# Microcontroller.net
KiCad netlist of a schematic drawn in Altium Designer
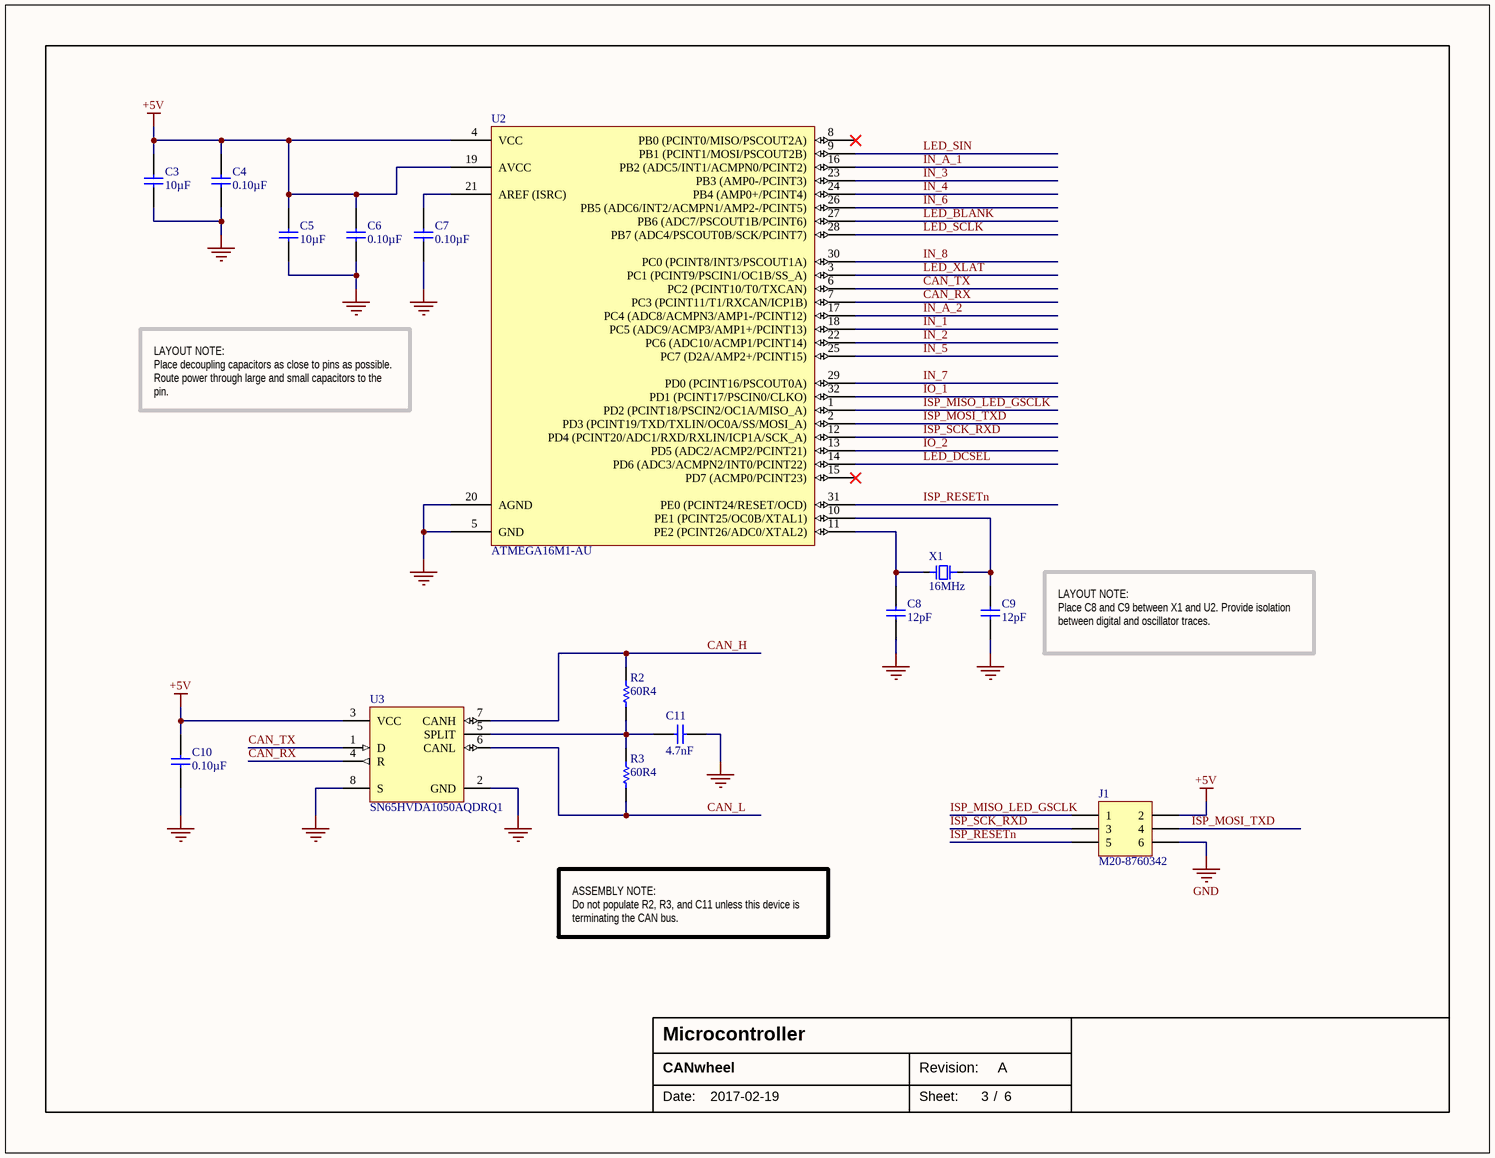
[diagram p0: Microcontroller.SchDoc]

(export (version "E")
  (design (tool "Eeschema 10.0.6"))
  (components
    (comp (ref "C3")
      (value "10µF")
      (footprint "CAP-0805-M")
      (fields
        (field (name "PART NUMBER") "CC0805KKX7R5BB106")
        (field (name "TOLERANCE") "±10%")
        (field (name "VOLTAGE") "6.3V")
      )
      (libsource (lib "Capacitors") (part "Capacitor"))
    )
    (comp (ref "C4")
      (value "0.10µF")
      (footprint "CAP-0402-M")
      (fields
        (field (name "PART NUMBER") "CC0402KRX7R5BB104")
        (field (name "TOLERANCE") "±10%")
        (field (name "VOLTAGE") "6.3V")
      )
      (libsource (lib "Capacitors") (part "Capacitor"))
    )
    (comp (ref "C5")
      (value "10µF")
      (footprint "CAP-0805-M")
      (fields
        (field (name "PART NUMBER") "CC0805KKX7R5BB106")
        (field (name "TOLERANCE") "±10%")
        (field (name "VOLTAGE") "6.3V")
      )
      (libsource (lib "Capacitors") (part "Capacitor"))
    )
    (comp (ref "C6")
      (value "0.10µF")
      (footprint "CAP-0402-M")
      (fields
        (field (name "PART NUMBER") "CC0402KRX7R5BB104")
        (field (name "TOLERANCE") "±10%")
        (field (name "VOLTAGE") "6.3V")
      )
      (libsource (lib "Capacitors") (part "Capacitor"))
    )
    (comp (ref "C7")
      (value "0.10µF")
      (footprint "CAP-0402-M")
      (fields
        (field (name "PART NUMBER") "CC0402KRX7R5BB104")
        (field (name "TOLERANCE") "±10%")
        (field (name "VOLTAGE") "6.3V")
      )
      (libsource (lib "Capacitors") (part "Capacitor"))
    )
    (comp (ref "C8")
      (value "12pF")
      (footprint "CAP-0402-M")
      (fields
        (field (name "PART NUMBER") "CC0402JRNPO9BN120")
        (field (name "TOLERANCE") "±5%")
        (field (name "VOLTAGE") "50V")
      )
      (libsource (lib "Capacitors") (part "Capacitor"))
    )
    (comp (ref "C9")
      (value "12pF")
      (footprint "CAP-0402-M")
      (fields
        (field (name "PART NUMBER") "CC0402JRNPO9BN120")
        (field (name "TOLERANCE") "±5%")
        (field (name "VOLTAGE") "50V")
      )
      (libsource (lib "Capacitors") (part "Capacitor"))
    )
    (comp (ref "C10")
      (value "0.10µF")
      (footprint "CAP-0402-M")
      (fields
        (field (name "PART NUMBER") "CC0402KRX7R5BB104")
        (field (name "TOLERANCE") "±10%")
        (field (name "VOLTAGE") "6.3V")
      )
      (libsource (lib "Capacitors") (part "Capacitor"))
    )
    (comp (ref "C11")
      (value "4.7nF")
      (footprint "CAP-0402-M")
      (fields
        (field (name "PART NUMBER") "CC0402KRX7R7BB472")
        (field (name "TOLERANCE") "±10%")
        (field (name "VOLTAGE") "16V")
      )
      (libsource (lib "Capacitors") (part "Capacitor"))
    )
    (comp (ref "J1")
      (value "M20-8760342")
      (footprint "M20-8760342")
      (libsource (lib "Connectors") (part "M20-8760342"))
    )
    (comp (ref "R2")
      (value "60R4")
      (footprint "RES-0805-M")
      (fields
        (field (name "PART NUMBER") "RC0805FR-0760R4L")
        (field (name "TOLERANCE") "1%")
        (field (name "POWER") "1/8 W")
      )
      (libsource (lib "Resistors") (part "Resistor"))
    )
    (comp (ref "R3")
      (value "60R4")
      (footprint "RES-0805-M")
      (fields
        (field (name "PART NUMBER") "RC0805FR-0760R4L")
        (field (name "TOLERANCE") "1%")
        (field (name "POWER") "1/8 W")
      )
      (libsource (lib "Resistors") (part "Resistor"))
    )
    (comp (ref "U2")
      (value "ATMEGA16M1-AU")
      (footprint "TQFP80P900X900X120-32N")
      (description "ATmega16M1 32-QFP 7x7 mm")
      (libsource (lib "CANwheel") (part "ATMEGA16M1-AU"))
    )
    (comp (ref "U3")
      (value "SN65HVDA1050AQDRQ1")
      (footprint "SOIC127P600X175-8M")
      (description "CAN transceiver")
      (libsource (lib "CANwheel") (part "SN65HVDA1050AQDRQ1"))
    )
    (comp (ref "X1")
      (value "16MHz")
      (footprint "SON127P500X135-2N")
      (description "SMD Crystal Oscillator 12 pF")
      (fields (field (name "Comment") "7A-16.000MAAE-T"))
      (libsource (lib "CANio") (part "7A-16.000MAAE-T"))
    )
  )
  (nets
    (net (code "1") (name "+5V") (class "Default")
      (node (ref "C10") (pin "1") (pinfunction "1_1") (pintype "passive"))
      (node (ref "C3") (pin "1") (pinfunction "1_1") (pintype "passive"))
      (node (ref "C4") (pin "1") (pinfunction "1_1") (pintype "passive"))
      (node (ref "C5") (pin "1") (pinfunction "1_1") (pintype "passive"))
      (node (ref "C6") (pin "1") (pinfunction "1_1") (pintype "passive"))
      (node (ref "J1") (pin "2") (pinfunction "2_2") (pintype "passive"))
      (node (ref "U2") (pin "19") (pinfunction "AVCC_19") (pintype "power_in"))
      (node (ref "U2") (pin "4") (pinfunction "VCC_4") (pintype "power_in"))
      (node (ref "U3") (pin "3") (pinfunction "VCC_3") (pintype "power_in"))
    )
    (net (code "2") (name "/CAN_H") (class "Default")
      (node (ref "R2") (pin "1") (pinfunction "1_1") (pintype "passive"))
      (node (ref "U3") (pin "7") (pinfunction "CANH_7") (pintype "bidirectional"))
    )
    (net (code "3") (name "/CAN_L") (class "Default")
      (node (ref "R3") (pin "1") (pinfunction "1_1") (pintype "passive"))
      (node (ref "U3") (pin "6") (pinfunction "CANL_6") (pintype "bidirectional"))
    )
    (net (code "4") (name "/CAN_RX") (class "Default")
      (node (ref "U2") (pin "7") (pinfunction "PC3_(PCINT11/T1/RXCAN/ICP1B)_7") (pintype "bidirectional"))
      (node (ref "U3") (pin "4") (pinfunction "R_4") (pintype "output"))
    )
    (net (code "5") (name "/CAN_TX") (class "Default")
      (node (ref "U2") (pin "6") (pinfunction "PC2_(PCINT10/T0/TXCAN)_6") (pintype "bidirectional"))
      (node (ref "U3") (pin "1") (pinfunction "D_1") (pintype "input"))
    )
    (net (code "6") (name "/IN_1") (class "Default")
      (node (ref "U2") (pin "18") (pinfunction "PC5_(ADC9/ACMP3/AMP1+/PCINT13)_18") (pintype "bidirectional"))
    )
    (net (code "7") (name "/IN_2") (class "Default")
      (node (ref "U2") (pin "22") (pinfunction "PC6_(ADC10/ACMP1/PCINT14)_22") (pintype "bidirectional"))
    )
    (net (code "8") (name "/IN_3") (class "Default")
      (node (ref "U2") (pin "23") (pinfunction "PB3_(AMP0-/PCINT3)_23") (pintype "bidirectional"))
    )
    (net (code "9") (name "/IN_4") (class "Default")
      (node (ref "U2") (pin "24") (pinfunction "PB4_(AMP0+/PCINT4)_24") (pintype "bidirectional"))
    )
    (net (code "10") (name "/IN_5") (class "Default")
      (node (ref "U2") (pin "25") (pinfunction "PC7_(D2A/AMP2+/PCINT15)_25") (pintype "bidirectional"))
    )
    (net (code "11") (name "/IN_6") (class "Default")
      (node (ref "U2") (pin "26") (pinfunction "PB5_(ADC6/INT2/ACMPN1/AMP2-/PCINT5)_26") (pintype "bidirectional"))
    )
    (net (code "12") (name "/IN_7") (class "Default")
      (node (ref "U2") (pin "29") (pinfunction "PD0_(PCINT16/PSCOUT0A)_29") (pintype "bidirectional"))
    )
    (net (code "13") (name "/IN_8") (class "Default")
      (node (ref "U2") (pin "30") (pinfunction "PC0_(PCINT8/INT3/PSCOUT1A)_30") (pintype "bidirectional"))
    )
    (net (code "14") (name "/IN_A_1") (class "Default")
      (node (ref "U2") (pin "16") (pinfunction "PB2_(ADC5/INT1/ACMPN0/PCINT2)_16") (pintype "bidirectional"))
    )
    (net (code "15") (name "/IN_A_2") (class "Default")
      (node (ref "U2") (pin "17") (pinfunction "PC4_(ADC8/ACMPN3/AMP1-/PCINT12)_17") (pintype "bidirectional"))
    )
    (net (code "16") (name "/IO_1") (class "Default")
      (node (ref "U2") (pin "32") (pinfunction "PD1_(PCINT17/PSCIN0/CLKO)_32") (pintype "bidirectional"))
    )
    (net (code "17") (name "/IO_2") (class "Default")
      (node (ref "U2") (pin "13") (pinfunction "PD5_(ADC2/ACMP2/PCINT21)_13") (pintype "bidirectional"))
    )
    (net (code "18") (name "/ISP_MISO_LED_GSCLK") (class "Default")
      (node (ref "J1") (pin "1") (pinfunction "1_1") (pintype "passive"))
      (node (ref "U2") (pin "1") (pinfunction "PD2_(PCINT18/PSCIN2/OC1A/MISO_A)_1") (pintype "bidirectional"))
    )
    (net (code "19") (name "/ISP_MOSI_TXD") (class "Default")
      (node (ref "J1") (pin "4") (pinfunction "4_4") (pintype "passive"))
      (node (ref "U2") (pin "2") (pinfunction "PD3_(PCINT19/TXD/TXLIN/OC0A/SS/MOSI_A)_2") (pintype "bidirectional"))
    )
    (net (code "20") (name "/ISP_RESETn") (class "Default")
      (node (ref "J1") (pin "5") (pinfunction "5_5") (pintype "passive"))
      (node (ref "U2") (pin "31") (pinfunction "PE0_(PCINT24/RESET/OCD)_31") (pintype "bidirectional"))
    )
    (net (code "21") (name "/ISP_SCK_RXD") (class "Default")
      (node (ref "J1") (pin "3") (pinfunction "3_3") (pintype "passive"))
      (node (ref "U2") (pin "12") (pinfunction "PD4_(PCINT20/ADC1/RXD/RXLIN/ICP1A/SCK_A)_12") (pintype "bidirectional"))
    )
    (net (code "22") (name "/LED_BLANK") (class "Default")
      (node (ref "U2") (pin "27") (pinfunction "PB6_(ADC7/PSCOUT1B/PCINT6)_27") (pintype "bidirectional"))
    )
    (net (code "23") (name "/LED_DCSEL") (class "Default")
      (node (ref "U2") (pin "14") (pinfunction "PD6_(ADC3/ACMPN2/INT0/PCINT22)_14") (pintype "bidirectional"))
    )
    (net (code "24") (name "/LED_SCLK") (class "Default")
      (node (ref "U2") (pin "28") (pinfunction "PB7_(ADC4/PSCOUT0B/SCK/PCINT7)_28") (pintype "bidirectional"))
    )
    (net (code "25") (name "/LED_SIN") (class "Default")
      (node (ref "U2") (pin "9") (pinfunction "PB1_(PCINT1/MOSI/PSCOUT2B)_9") (pintype "bidirectional"))
    )
    (net (code "26") (name "/LED_XLAT") (class "Default")
      (node (ref "U2") (pin "3") (pinfunction "PC1_(PCINT9/PSCIN1/OC1B/SS_A)_3") (pintype "bidirectional"))
    )
    (net (code "27") (name "GND") (class "Default")
      (node (ref "C10") (pin "2") (pinfunction "2_2") (pintype "passive"))
      (node (ref "C11") (pin "1") (pinfunction "1_1") (pintype "passive"))
      (node (ref "C3") (pin "2") (pinfunction "2_2") (pintype "passive"))
      (node (ref "C4") (pin "2") (pinfunction "2_2") (pintype "passive"))
      (node (ref "C5") (pin "2") (pinfunction "2_2") (pintype "passive"))
      (node (ref "C6") (pin "2") (pinfunction "2_2") (pintype "passive"))
      (node (ref "C7") (pin "2") (pinfunction "2_2") (pintype "passive"))
      (node (ref "C8") (pin "1") (pinfunction "1_1") (pintype "passive"))
      (node (ref "C9") (pin "1") (pinfunction "1_1") (pintype "passive"))
      (node (ref "J1") (pin "6") (pinfunction "6_6") (pintype "passive"))
      (node (ref "U2") (pin "20") (pinfunction "AGND_20") (pintype "power_in"))
      (node (ref "U2") (pin "5") (pinfunction "GND_5") (pintype "power_in"))
      (node (ref "U3") (pin "2") (pinfunction "GND_2") (pintype "power_in"))
      (node (ref "U3") (pin "8") (pinfunction "S_8") (pintype "passive"))
    )
    (net (code "28") (name "Net-(U2-AREF_(ISRC))") (class "Default")
      (node (ref "C7") (pin "1") (pinfunction "1_1") (pintype "passive"))
      (node (ref "U2") (pin "21") (pinfunction "AREF_(ISRC)_21") (pintype "power_in"))
    )
    (net (code "29") (name "Net-(U2-PE1_(PCINT25{slash}OC0B{slash}XTAL1))") (class "Default")
      (node (ref "C9") (pin "2") (pinfunction "2_2") (pintype "passive"))
      (node (ref "U2") (pin "10") (pinfunction "PE1_(PCINT25/OC0B/XTAL1)_10") (pintype "bidirectional"))
      (node (ref "X1") (pin "1") (pinfunction "1_1") (pintype "passive"))
    )
    (net (code "30") (name "Net-(U2-PE2_(PCINT26{slash}ADC0{slash}XTAL2))") (class "Default")
      (node (ref "C8") (pin "2") (pinfunction "2_2") (pintype "passive"))
      (node (ref "U2") (pin "11") (pinfunction "PE2_(PCINT26/ADC0/XTAL2)_11") (pintype "bidirectional"))
      (node (ref "X1") (pin "2") (pinfunction "2_2") (pintype "passive"))
    )
    (net (code "31") (name "Net-(U3-SPLIT)") (class "Default")
      (node (ref "C11") (pin "2") (pinfunction "2_2") (pintype "passive"))
      (node (ref "R2") (pin "2") (pinfunction "2_2") (pintype "passive"))
      (node (ref "R3") (pin "2") (pinfunction "2_2") (pintype "passive"))
      (node (ref "U3") (pin "5") (pinfunction "SPLIT_5") (pintype "passive"))
    )
    (net (code "32") (name "unconnected-(U2-PB0_(PCINT0{slash}MISO{slash}PSCOUT2A)-Pad8)") (class "Default")
      (node (ref "U2") (pin "8") (pinfunction "PB0_(PCINT0/MISO/PSCOUT2A)_8") (pintype "bidirectional+no_connect"))
    )
    (net (code "33") (name "unconnected-(U2-PD7_(ACMP0{slash}PCINT23)-Pad15)") (class "Default")
      (node (ref "U2") (pin "15") (pinfunction "PD7_(ACMP0/PCINT23)_15") (pintype "bidirectional+no_connect"))
    )
  )
)
